# satshakit-mega.net
KiCad netlist of a schematic drawn in EAGLE
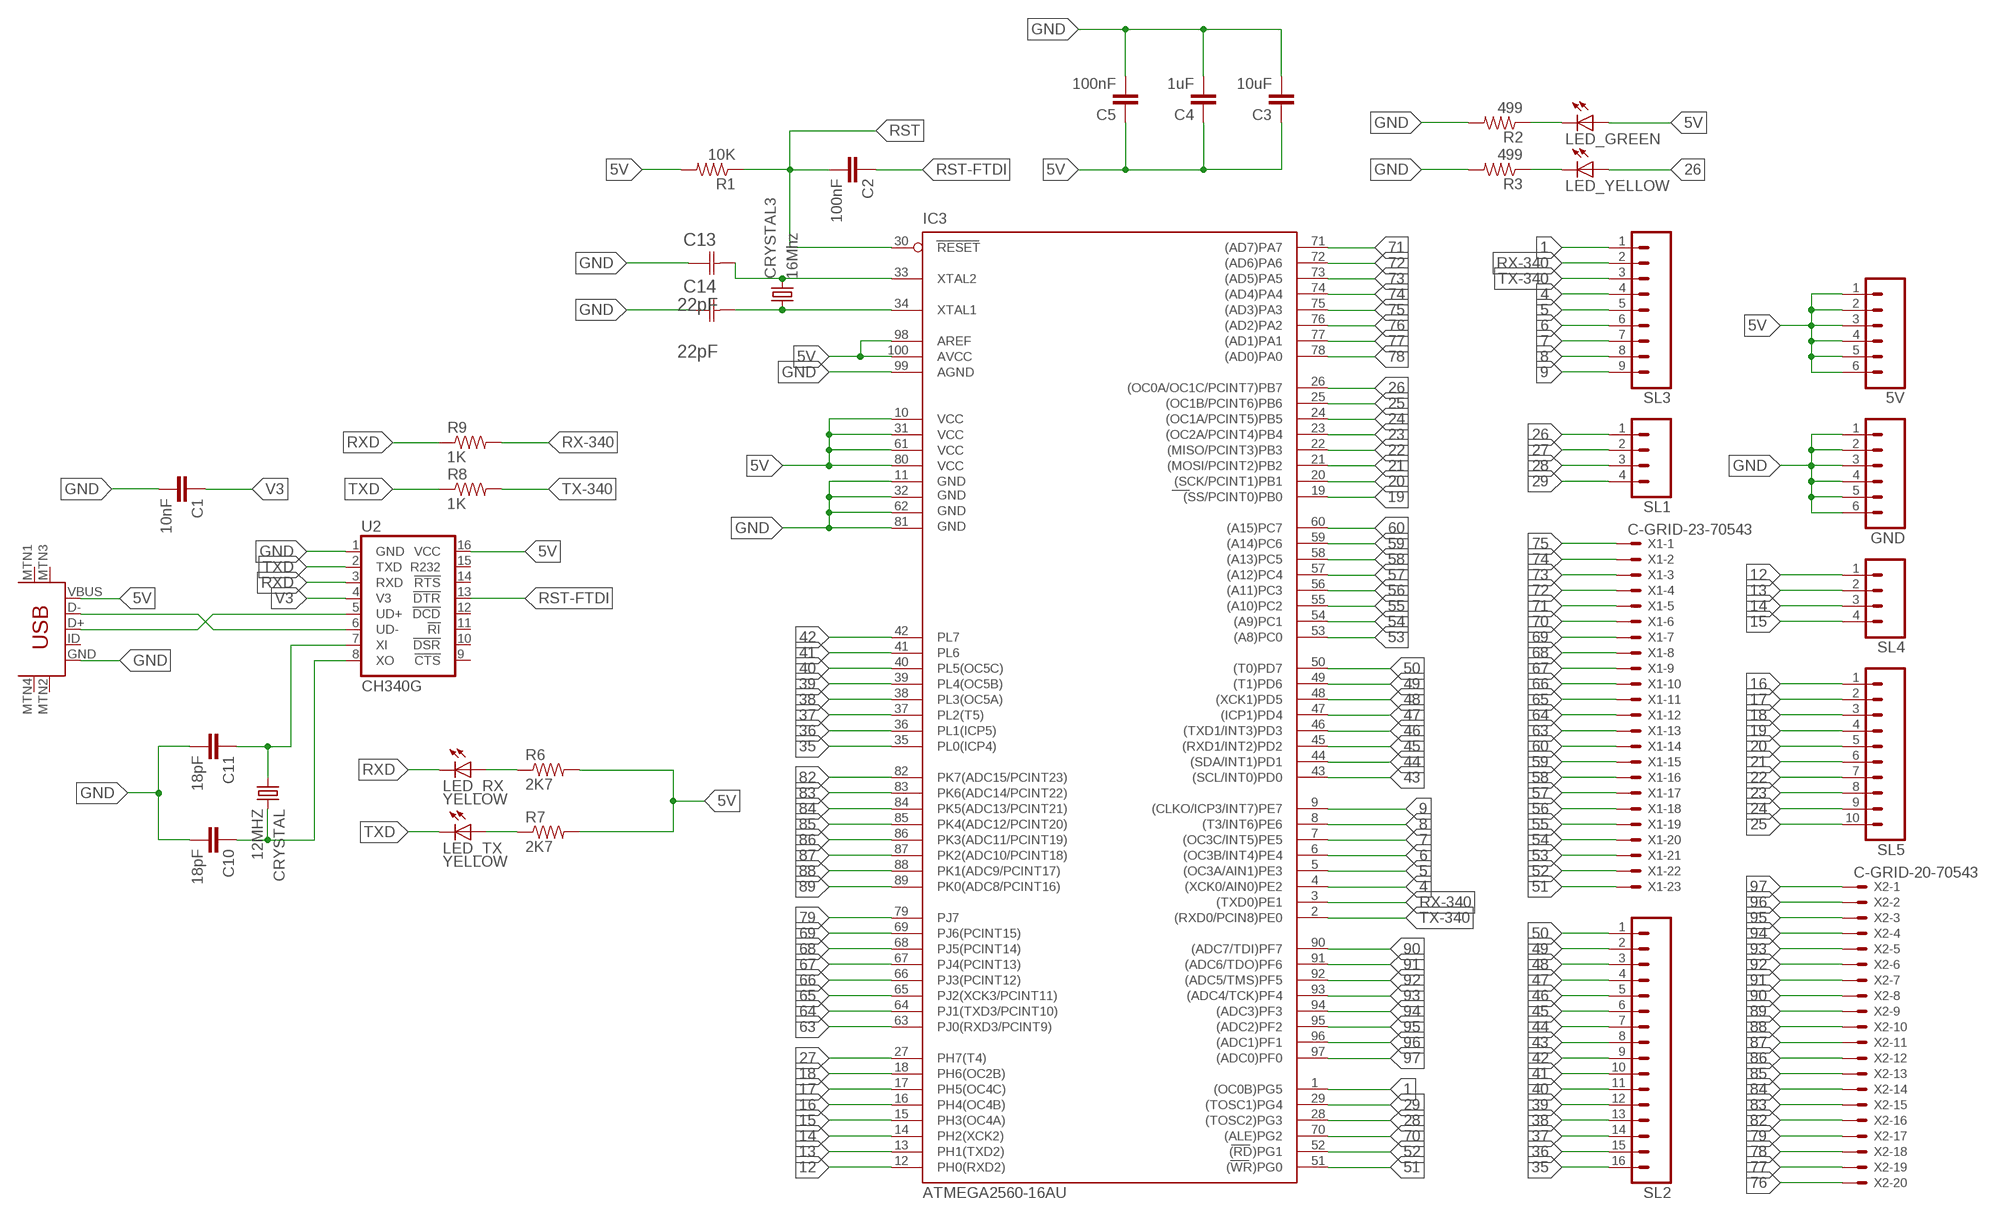
[diagram p0: schematic, sheet 1]

(export (version "E")
  (design (tool "Eeschema 10.0.6"))
  (components
    (comp (ref "5V")
      (value "M06")
      (footprint "eagle-import:06P")
      (libsource (lib "eagle-import") (part "M06"))
    )
    (comp (ref "C1")
      (value "10nF")
      (footprint "eagle-import:1206")
      (libsource (lib "eagle-import") (part "CAP1206"))
    )
    (comp (ref "C2")
      (value "100nF")
      (footprint "eagle-import:1206")
      (libsource (lib "eagle-import") (part "CAP1206"))
    )
    (comp (ref "C3")
      (value "10uF")
      (footprint "eagle-import:1206")
      (libsource (lib "eagle-import") (part "CAP1206"))
    )
    (comp (ref "C4")
      (value "1uF")
      (footprint "eagle-import:1206")
      (libsource (lib "eagle-import") (part "CAP1206"))
    )
    (comp (ref "C5")
      (value "100nF")
      (footprint "eagle-import:1206")
      (libsource (lib "eagle-import") (part "CAP1206"))
    )
    (comp (ref "C10")
      (value "18pF")
      (footprint "eagle-import:1206")
      (libsource (lib "eagle-import") (part "CAP1206"))
    )
    (comp (ref "C11")
      (value "18pF")
      (footprint "eagle-import:1206")
      (libsource (lib "eagle-import") (part "CAP1206"))
    )
    (comp (ref "C13")
      (value "22pF")
      (footprint "eagle-import:CAPC3216X178N")
      (fields (field (name "MPN") "0612ZC225MAT2A") (field (name "TOLERANCE") "±20%"))
      (libsource (lib "eagle-import") (part "0612ZC225MAT2A"))
    )
    (comp (ref "C14")
      (value "22pF")
      (footprint "eagle-import:CAPC3216X178N")
      (fields (field (name "MPN") "0612ZC225MAT2A") (field (name "TOLERANCE") "±20%"))
      (libsource (lib "eagle-import") (part "0612ZC225MAT2A"))
    )
    (comp (ref "CRYSTAL")
      (value "12MHZ")
      (footprint "eagle-import:CSM-7X-DU")
      (libsource (lib "eagle-import") (part "flight_controller.lbr01_FAB_Hello_CSM-7X-DU"))
    )
    (comp (ref "CRYSTAL3")
      (value "16Mhz")
      (footprint "eagle-import:CSM-7X-DU")
      (libsource (lib "eagle-import") (part "CSM-7X-DU"))
    )
    (comp (ref "GND")
      (value "M06")
      (footprint "eagle-import:06P")
      (libsource (lib "eagle-import") (part "M06"))
    )
    (comp (ref "IC3")
      (value "ATMEGA2560-16AU")
      (footprint "eagle-import:TQFP100")
      (libsource (lib "eagle-import") (part "ATMEGAAU1280-16"))
    )
    (comp (ref "LED_GREEN")
      (value "LED1206")
      (footprint "eagle-import:1206")
      (libsource (lib "eagle-import") (part "LED1206"))
    )
    (comp (ref "LED_RX")
      (value "YELLOW")
      (footprint "eagle-import:LED1206")
      (libsource (lib "eagle-import") (part "LED"))
    )
    (comp (ref "LED_TX")
      (value "YELLOW")
      (footprint "eagle-import:LED1206")
      (libsource (lib "eagle-import") (part "LED"))
    )
    (comp (ref "LED_YELLOW")
      (value "LED1206")
      (footprint "eagle-import:1206")
      (libsource (lib "eagle-import") (part "LED1206"))
    )
    (comp (ref "R1")
      (value "10K")
      (footprint "eagle-import:R1206")
      (libsource (lib "eagle-import") (part "RES-US1206"))
    )
    (comp (ref "R2")
      (value "499")
      (footprint "eagle-import:1206")
      (libsource (lib "eagle-import") (part "RESISTOR1206"))
    )
    (comp (ref "R3")
      (value "499")
      (footprint "eagle-import:1206")
      (libsource (lib "eagle-import") (part "RESISTOR1206"))
    )
    (comp (ref "R6")
      (value "2K7")
      (footprint "eagle-import:R1206")
      (libsource (lib "eagle-import") (part "RES-US1206"))
    )
    (comp (ref "R7")
      (value "2K7")
      (footprint "eagle-import:R1206")
      (libsource (lib "eagle-import") (part "RES-US1206"))
    )
    (comp (ref "R8")
      (value "1K")
      (footprint "eagle-import:R1206")
      (libsource (lib "eagle-import") (part "RES-US1206"))
    )
    (comp (ref "R9")
      (value "1K")
      (footprint "eagle-import:R1206")
      (libsource (lib "eagle-import") (part "RES-US1206"))
    )
    (comp (ref "SL1")
      (value "M04")
      (footprint "eagle-import:04P")
      (libsource (lib "eagle-import") (part "M04"))
    )
    (comp (ref "SL2")
      (value "M16")
      (footprint "eagle-import:16P")
      (libsource (lib "eagle-import") (part "M16"))
    )
    (comp (ref "SL3")
      (value "M09")
      (footprint "eagle-import:09P")
      (libsource (lib "eagle-import") (part "M09"))
    )
    (comp (ref "SL4")
      (value "M04")
      (footprint "eagle-import:04P")
      (libsource (lib "eagle-import") (part "M04"))
    )
    (comp (ref "SL5")
      (value "M10")
      (footprint "eagle-import:10P")
      (libsource (lib "eagle-import") (part "M10"))
    )
    (comp (ref "U$7")
      (value "USB-MINIB-5PIN")
      (footprint "eagle-import:USB-MINIB")
      (libsource (lib "eagle-import") (part "USB-MINIB-5PIN"))
    )
    (comp (ref "U2")
      (value "CH340G")
      (footprint "eagle-import:SO016")
      (libsource (lib "eagle-import") (part "CH340GSMD"))
    )
    (comp (ref "X1")
      (value "C-GRID-23-70543")
      (footprint "eagle-import:70543-23")
      (libsource (lib "eagle-import") (part "C-GRID-23-70543"))
    )
    (comp (ref "X2")
      (value "C-GRID-20-70543")
      (footprint "eagle-import:70543-20")
      (libsource (lib "eagle-import") (part "C-GRID-20-70543"))
    )
  )
  (nets
    (net (code "1") (name "1") (class "Default")
      (node (ref "IC3") (pin "1") (pinfunction "(OC0B)PG5_1") (pintype "bidirectional"))
      (node (ref "SL3") (pin "1") (pinfunction "1_1") (pintype "passive"))
    )
    (net (code "2") (name "4") (class "Default")
      (node (ref "IC3") (pin "4") (pinfunction "(XCK0/AIN0)PE2_4") (pintype "bidirectional"))
      (node (ref "SL3") (pin "4") (pinfunction "4_4") (pintype "passive"))
    )
    (net (code "3") (name "5") (class "Default")
      (node (ref "IC3") (pin "5") (pinfunction "(OC3A/AIN1)PE3_5") (pintype "bidirectional"))
      (node (ref "SL3") (pin "5") (pinfunction "5_5") (pintype "passive"))
    )
    (net (code "4") (name "5V") (class "Default")
      (node (ref "5V") (pin "1") (pinfunction "1_1") (pintype "passive"))
      (node (ref "5V") (pin "2") (pinfunction "2_2") (pintype "passive"))
      (node (ref "5V") (pin "3") (pinfunction "3_3") (pintype "passive"))
      (node (ref "5V") (pin "4") (pinfunction "4_4") (pintype "passive"))
      (node (ref "5V") (pin "5") (pinfunction "5_5") (pintype "passive"))
      (node (ref "5V") (pin "6") (pinfunction "6_6") (pintype "passive"))
      (node (ref "C3") (pin "1") (pinfunction "1_1") (pintype "passive"))
      (node (ref "C4") (pin "1") (pinfunction "1_1") (pintype "passive"))
      (node (ref "C5") (pin "1") (pinfunction "1_1") (pintype "passive"))
      (node (ref "IC3") (pin "10") (pinfunction "VCC_10") (pintype "power_in"))
      (node (ref "IC3") (pin "100") (pinfunction "AVCC_100") (pintype "power_in"))
      (node (ref "IC3") (pin "31") (pinfunction "VCC1_31") (pintype "power_in"))
      (node (ref "IC3") (pin "61") (pinfunction "VCC2_61") (pintype "power_in"))
      (node (ref "IC3") (pin "80") (pinfunction "VCC3_80") (pintype "power_in"))
      (node (ref "IC3") (pin "98") (pinfunction "AREF_98") (pintype "bidirectional"))
      (node (ref "LED_GREEN") (pin "1") (pinfunction "A_1") (pintype "passive"))
      (node (ref "R1") (pin "2") (pinfunction "2_2") (pintype "passive"))
      (node (ref "R6") (pin "2") (pinfunction "2_2") (pintype "passive"))
      (node (ref "R7") (pin "2") (pinfunction "2_2") (pintype "passive"))
      (node (ref "U$7") (pin "VBUS") (pinfunction "VBUS_VBUS") (pintype "bidirectional"))
      (node (ref "U2") (pin "16") (pinfunction "VCC_16") (pintype "bidirectional"))
    )
    (net (code "5") (name "6") (class "Default")
      (node (ref "IC3") (pin "6") (pinfunction "(OC3B/INT4)PE4_6") (pintype "bidirectional"))
      (node (ref "SL3") (pin "6") (pinfunction "6_6") (pintype "passive"))
    )
    (net (code "6") (name "7") (class "Default")
      (node (ref "IC3") (pin "7") (pinfunction "(OC3C/INT5)PE5_7") (pintype "bidirectional"))
      (node (ref "SL3") (pin "7") (pinfunction "7_7") (pintype "passive"))
    )
    (net (code "7") (name "8") (class "Default")
      (node (ref "IC3") (pin "8") (pinfunction "(T3/INT6)PE6_8") (pintype "bidirectional"))
      (node (ref "SL3") (pin "8") (pinfunction "8_8") (pintype "passive"))
    )
    (net (code "8") (name "9") (class "Default")
      (node (ref "IC3") (pin "9") (pinfunction "(CLKO/ICP3/INT7)PE7_9") (pintype "bidirectional"))
      (node (ref "SL3") (pin "9") (pinfunction "9_9") (pintype "passive"))
    )
    (net (code "9") (name "12") (class "Default")
      (node (ref "IC3") (pin "12") (pinfunction "PH0(RXD2)_12") (pintype "bidirectional"))
      (node (ref "SL4") (pin "1") (pinfunction "1_1") (pintype "passive"))
    )
    (net (code "10") (name "13") (class "Default")
      (node (ref "IC3") (pin "13") (pinfunction "PH1(TXD2)_13") (pintype "bidirectional"))
      (node (ref "SL4") (pin "2") (pinfunction "2_2") (pintype "passive"))
    )
    (net (code "11") (name "14") (class "Default")
      (node (ref "IC3") (pin "14") (pinfunction "PH2(XCK2)_14") (pintype "bidirectional"))
      (node (ref "SL4") (pin "3") (pinfunction "3_3") (pintype "passive"))
    )
    (net (code "12") (name "15") (class "Default")
      (node (ref "IC3") (pin "15") (pinfunction "PH3(OC4A)_15") (pintype "bidirectional"))
      (node (ref "SL4") (pin "4") (pinfunction "4_4") (pintype "passive"))
    )
    (net (code "13") (name "16") (class "Default")
      (node (ref "IC3") (pin "16") (pinfunction "PH4(OC4B)_16") (pintype "bidirectional"))
      (node (ref "SL5") (pin "1") (pinfunction "1_1") (pintype "passive"))
    )
    (net (code "14") (name "17") (class "Default")
      (node (ref "IC3") (pin "17") (pinfunction "PH5(OC4C)_17") (pintype "bidirectional"))
      (node (ref "SL5") (pin "2") (pinfunction "2_2") (pintype "passive"))
    )
    (net (code "15") (name "18") (class "Default")
      (node (ref "IC3") (pin "18") (pinfunction "PH6(OC2B)_18") (pintype "bidirectional"))
      (node (ref "SL5") (pin "3") (pinfunction "3_3") (pintype "passive"))
    )
    (net (code "16") (name "19") (class "Default")
      (node (ref "IC3") (pin "19") (pinfunction "(SS/PCINT0)PB0_19") (pintype "bidirectional"))
      (node (ref "SL5") (pin "4") (pinfunction "4_4") (pintype "passive"))
    )
    (net (code "17") (name "20") (class "Default")
      (node (ref "IC3") (pin "20") (pinfunction "(SCK/PCINT1)PB1_20") (pintype "bidirectional"))
      (node (ref "SL5") (pin "5") (pinfunction "5_5") (pintype "passive"))
    )
    (net (code "18") (name "21") (class "Default")
      (node (ref "IC3") (pin "21") (pinfunction "(MOSI/PCINT2)PB2_21") (pintype "bidirectional"))
      (node (ref "SL5") (pin "6") (pinfunction "6_6") (pintype "passive"))
    )
    (net (code "19") (name "22") (class "Default")
      (node (ref "IC3") (pin "22") (pinfunction "(MISO/PCINT3)PB3_22") (pintype "bidirectional"))
      (node (ref "SL5") (pin "7") (pinfunction "7_7") (pintype "passive"))
    )
    (net (code "20") (name "23") (class "Default")
      (node (ref "IC3") (pin "23") (pinfunction "(OC2A/PCINT4)PB4_23") (pintype "bidirectional"))
      (node (ref "SL5") (pin "8") (pinfunction "8_8") (pintype "passive"))
    )
    (net (code "21") (name "24") (class "Default")
      (node (ref "IC3") (pin "24") (pinfunction "(OC1A/PCINT5)PB5_24") (pintype "bidirectional"))
      (node (ref "SL5") (pin "9") (pinfunction "9_9") (pintype "passive"))
    )
    (net (code "22") (name "25") (class "Default")
      (node (ref "IC3") (pin "25") (pinfunction "(OC1B/PCINT6)PB6_25") (pintype "bidirectional"))
      (node (ref "SL5") (pin "10") (pinfunction "10_10") (pintype "passive"))
    )
    (net (code "23") (name "26") (class "Default")
      (node (ref "IC3") (pin "26") (pinfunction "(OC0A/OC1C/PCINT7)PB7_26") (pintype "bidirectional"))
      (node (ref "LED_YELLOW") (pin "1") (pinfunction "A_1") (pintype "passive"))
      (node (ref "SL1") (pin "1") (pinfunction "1_1") (pintype "passive"))
    )
    (net (code "24") (name "27") (class "Default")
      (node (ref "IC3") (pin "27") (pinfunction "PH7(T4)_27") (pintype "bidirectional"))
      (node (ref "SL1") (pin "2") (pinfunction "2_2") (pintype "passive"))
    )
    (net (code "25") (name "28") (class "Default")
      (node (ref "IC3") (pin "28") (pinfunction "(TOSC2)PG3_28") (pintype "bidirectional"))
      (node (ref "SL1") (pin "3") (pinfunction "3_3") (pintype "passive"))
    )
    (net (code "26") (name "29") (class "Default")
      (node (ref "IC3") (pin "29") (pinfunction "(TOSC1)PG4_29") (pintype "bidirectional"))
      (node (ref "SL1") (pin "4") (pinfunction "4_4") (pintype "passive"))
    )
    (net (code "27") (name "35") (class "Default")
      (node (ref "IC3") (pin "35") (pinfunction "PL0(ICP4)_35") (pintype "bidirectional"))
      (node (ref "SL2") (pin "16") (pinfunction "16_16") (pintype "passive"))
    )
    (net (code "28") (name "36") (class "Default")
      (node (ref "IC3") (pin "36") (pinfunction "PL1(ICP5)_36") (pintype "bidirectional"))
      (node (ref "SL2") (pin "15") (pinfunction "15_15") (pintype "passive"))
    )
    (net (code "29") (name "37") (class "Default")
      (node (ref "IC3") (pin "37") (pinfunction "PL2(T5)_37") (pintype "bidirectional"))
      (node (ref "SL2") (pin "14") (pinfunction "14_14") (pintype "passive"))
    )
    (net (code "30") (name "38") (class "Default")
      (node (ref "IC3") (pin "38") (pinfunction "PL3(OC5A)_38") (pintype "bidirectional"))
      (node (ref "SL2") (pin "13") (pinfunction "13_13") (pintype "passive"))
    )
    (net (code "31") (name "39") (class "Default")
      (node (ref "IC3") (pin "39") (pinfunction "PL4(OC5B)_39") (pintype "bidirectional"))
      (node (ref "SL2") (pin "12") (pinfunction "12_12") (pintype "passive"))
    )
    (net (code "32") (name "40") (class "Default")
      (node (ref "IC3") (pin "40") (pinfunction "PL5(OC5C)_40") (pintype "bidirectional"))
      (node (ref "SL2") (pin "11") (pinfunction "11_11") (pintype "passive"))
    )
    (net (code "33") (name "41") (class "Default")
      (node (ref "IC3") (pin "41") (pinfunction "PL6_41") (pintype "bidirectional"))
      (node (ref "SL2") (pin "10") (pinfunction "10_10") (pintype "passive"))
    )
    (net (code "34") (name "42") (class "Default")
      (node (ref "IC3") (pin "42") (pinfunction "PL7_42") (pintype "bidirectional"))
      (node (ref "SL2") (pin "9") (pinfunction "9_9") (pintype "passive"))
    )
    (net (code "35") (name "43") (class "Default")
      (node (ref "IC3") (pin "43") (pinfunction "(SCL/INT0)PD0_43") (pintype "bidirectional"))
      (node (ref "SL2") (pin "8") (pinfunction "8_8") (pintype "passive"))
    )
    (net (code "36") (name "44") (class "Default")
      (node (ref "IC3") (pin "44") (pinfunction "(SDA/INT1)PD1_44") (pintype "bidirectional"))
      (node (ref "SL2") (pin "7") (pinfunction "7_7") (pintype "passive"))
    )
    (net (code "37") (name "45") (class "Default")
      (node (ref "IC3") (pin "45") (pinfunction "(RXD1/INT2)PD2_45") (pintype "bidirectional"))
      (node (ref "SL2") (pin "6") (pinfunction "6_6") (pintype "passive"))
    )
    (net (code "38") (name "46") (class "Default")
      (node (ref "IC3") (pin "46") (pinfunction "(TXD1/INT3)PD3_46") (pintype "bidirectional"))
      (node (ref "SL2") (pin "5") (pinfunction "5_5") (pintype "passive"))
    )
    (net (code "39") (name "47") (class "Default")
      (node (ref "IC3") (pin "47") (pinfunction "(ICP1)PD4_47") (pintype "bidirectional"))
      (node (ref "SL2") (pin "4") (pinfunction "4_4") (pintype "passive"))
    )
    (net (code "40") (name "48") (class "Default")
      (node (ref "IC3") (pin "48") (pinfunction "(XCK1)PD5_48") (pintype "bidirectional"))
      (node (ref "SL2") (pin "3") (pinfunction "3_3") (pintype "passive"))
    )
    (net (code "41") (name "49") (class "Default")
      (node (ref "IC3") (pin "49") (pinfunction "(T1)PD6_49") (pintype "bidirectional"))
      (node (ref "SL2") (pin "2") (pinfunction "2_2") (pintype "passive"))
    )
    (net (code "42") (name "50") (class "Default")
      (node (ref "IC3") (pin "50") (pinfunction "(T0)PD7_50") (pintype "bidirectional"))
      (node (ref "SL2") (pin "1") (pinfunction "1_1") (pintype "passive"))
    )
    (net (code "43") (name "51") (class "Default")
      (node (ref "IC3") (pin "51") (pinfunction "(WR)PG0_51") (pintype "bidirectional"))
      (node (ref "X1") (pin "23") (pinfunction "S_23") (pintype "passive"))
    )
    (net (code "44") (name "52") (class "Default")
      (node (ref "IC3") (pin "52") (pinfunction "(RD)PG1_52") (pintype "bidirectional"))
      (node (ref "X1") (pin "22") (pinfunction "S_22") (pintype "passive"))
    )
    (net (code "45") (name "53") (class "Default")
      (node (ref "IC3") (pin "53") (pinfunction "(A8)PC0_53") (pintype "bidirectional"))
      (node (ref "X1") (pin "21") (pinfunction "S_21") (pintype "passive"))
    )
    (net (code "46") (name "54") (class "Default")
      (node (ref "IC3") (pin "54") (pinfunction "(A9)PC1_54") (pintype "bidirectional"))
      (node (ref "X1") (pin "20") (pinfunction "S_20") (pintype "passive"))
    )
    (net (code "47") (name "55") (class "Default")
      (node (ref "IC3") (pin "55") (pinfunction "(A10)PC2_55") (pintype "bidirectional"))
      (node (ref "X1") (pin "19") (pinfunction "S_19") (pintype "passive"))
    )
    (net (code "48") (name "56") (class "Default")
      (node (ref "IC3") (pin "56") (pinfunction "(A11)PC3_56") (pintype "bidirectional"))
      (node (ref "X1") (pin "18") (pinfunction "S_18") (pintype "passive"))
    )
    (net (code "49") (name "57") (class "Default")
      (node (ref "IC3") (pin "57") (pinfunction "(A12)PC4_57") (pintype "bidirectional"))
      (node (ref "X1") (pin "17") (pinfunction "S_17") (pintype "passive"))
    )
    (net (code "50") (name "58") (class "Default")
      (node (ref "IC3") (pin "58") (pinfunction "(A13)PC5_58") (pintype "bidirectional"))
      (node (ref "X1") (pin "16") (pinfunction "S_16") (pintype "passive"))
    )
    (net (code "51") (name "59") (class "Default")
      (node (ref "IC3") (pin "59") (pinfunction "(A14)PC6_59") (pintype "bidirectional"))
      (node (ref "X1") (pin "15") (pinfunction "S_15") (pintype "passive"))
    )
    (net (code "52") (name "60") (class "Default")
      (node (ref "IC3") (pin "60") (pinfunction "(A15)PC7_60") (pintype "bidirectional"))
      (node (ref "X1") (pin "14") (pinfunction "S_14") (pintype "passive"))
    )
    (net (code "53") (name "63") (class "Default")
      (node (ref "IC3") (pin "63") (pinfunction "PJ0(RXD3/PCINT9)_63") (pintype "bidirectional"))
      (node (ref "X1") (pin "13") (pinfunction "S_13") (pintype "passive"))
    )
    (net (code "54") (name "64") (class "Default")
      (node (ref "IC3") (pin "64") (pinfunction "PJ1(TXD3/PCINT10)_64") (pintype "bidirectional"))
      (node (ref "X1") (pin "12") (pinfunction "S_12") (pintype "passive"))
    )
    (net (code "55") (name "65") (class "Default")
      (node (ref "IC3") (pin "65") (pinfunction "PJ2(XCK3/PCINT11)_65") (pintype "bidirectional"))
      (node (ref "X1") (pin "11") (pinfunction "S_11") (pintype "passive"))
    )
    (net (code "56") (name "66") (class "Default")
      (node (ref "IC3") (pin "66") (pinfunction "PJ3(PCINT12)_66") (pintype "bidirectional"))
      (node (ref "X1") (pin "10") (pinfunction "S_10") (pintype "passive"))
    )
    (net (code "57") (name "67") (class "Default")
      (node (ref "IC3") (pin "67") (pinfunction "PJ4(PCINT13)_67") (pintype "bidirectional"))
      (node (ref "X1") (pin "9") (pinfunction "S_9") (pintype "passive"))
    )
    (net (code "58") (name "68") (class "Default")
      (node (ref "IC3") (pin "68") (pinfunction "PJ5(PCINT14)_68") (pintype "bidirectional"))
      (node (ref "X1") (pin "8") (pinfunction "S_8") (pintype "passive"))
    )
    (net (code "59") (name "69") (class "Default")
      (node (ref "IC3") (pin "69") (pinfunction "PJ6(PCINT15)_69") (pintype "bidirectional"))
      (node (ref "X1") (pin "7") (pinfunction "S_7") (pintype "passive"))
    )
    (net (code "60") (name "70") (class "Default")
      (node (ref "IC3") (pin "70") (pinfunction "(ALE)PG2_70") (pintype "bidirectional"))
      (node (ref "X1") (pin "6") (pinfunction "S_6") (pintype "passive"))
    )
    (net (code "61") (name "71") (class "Default")
      (node (ref "IC3") (pin "71") (pinfunction "(AD7)PA7_71") (pintype "bidirectional"))
      (node (ref "X1") (pin "5") (pinfunction "S_5") (pintype "passive"))
    )
    (net (code "62") (name "72") (class "Default")
      (node (ref "IC3") (pin "72") (pinfunction "(AD6)PA6_72") (pintype "bidirectional"))
      (node (ref "X1") (pin "4") (pinfunction "S_4") (pintype "passive"))
    )
    (net (code "63") (name "73") (class "Default")
      (node (ref "IC3") (pin "73") (pinfunction "(AD5)PA5_73") (pintype "bidirectional"))
      (node (ref "X1") (pin "3") (pinfunction "S_3") (pintype "passive"))
    )
    (net (code "64") (name "74") (class "Default")
      (node (ref "IC3") (pin "74") (pinfunction "(AD4)PA4_74") (pintype "bidirectional"))
      (node (ref "X1") (pin "2") (pinfunction "S_2") (pintype "passive"))
    )
    (net (code "65") (name "75") (class "Default")
      (node (ref "IC3") (pin "75") (pinfunction "(AD3)PA3_75") (pintype "bidirectional"))
      (node (ref "X1") (pin "1") (pinfunction "S_1") (pintype "passive"))
    )
    (net (code "66") (name "76") (class "Default")
      (node (ref "IC3") (pin "76") (pinfunction "(AD2)PA2_76") (pintype "bidirectional"))
      (node (ref "X2") (pin "20") (pinfunction "S_20") (pintype "passive"))
    )
    (net (code "67") (name "77") (class "Default")
      (node (ref "IC3") (pin "77") (pinfunction "(AD1)PA1_77") (pintype "bidirectional"))
      (node (ref "X2") (pin "19") (pinfunction "S_19") (pintype "passive"))
    )
    (net (code "68") (name "78") (class "Default")
      (node (ref "IC3") (pin "78") (pinfunction "(AD0)PA0_78") (pintype "bidirectional"))
      (node (ref "X2") (pin "18") (pinfunction "S_18") (pintype "passive"))
    )
    (net (code "69") (name "79") (class "Default")
      (node (ref "IC3") (pin "79") (pinfunction "PJ7_79") (pintype "bidirectional"))
      (node (ref "X2") (pin "17") (pinfunction "S_17") (pintype "passive"))
    )
    (net (code "70") (name "82") (class "Default")
      (node (ref "IC3") (pin "82") (pinfunction "PK7(ADC15/PCINT23)_82") (pintype "bidirectional"))
      (node (ref "X2") (pin "16") (pinfunction "S_16") (pintype "passive"))
    )
    (net (code "71") (name "83") (class "Default")
      (node (ref "IC3") (pin "83") (pinfunction "PK6(ADC14/PCINT22)_83") (pintype "bidirectional"))
      (node (ref "X2") (pin "15") (pinfunction "S_15") (pintype "passive"))
    )
    (net (code "72") (name "84") (class "Default")
      (node (ref "IC3") (pin "84") (pinfunction "PK5(ADC13/PCINT21)_84") (pintype "bidirectional"))
      (node (ref "X2") (pin "14") (pinfunction "S_14") (pintype "passive"))
    )
    (net (code "73") (name "85") (class "Default")
      (node (ref "IC3") (pin "85") (pinfunction "PK4(ADC12/PCINT20)_85") (pintype "bidirectional"))
      (node (ref "X2") (pin "13") (pinfunction "S_13") (pintype "passive"))
    )
    (net (code "74") (name "86") (class "Default")
      (node (ref "IC3") (pin "86") (pinfunction "PK3(ADC11/PCINT19)_86") (pintype "bidirectional"))
      (node (ref "X2") (pin "12") (pinfunction "S_12") (pintype "passive"))
    )
    (net (code "75") (name "87") (class "Default")
      (node (ref "IC3") (pin "87") (pinfunction "PK2(ADC10/PCINT18)_87") (pintype "bidirectional"))
      (node (ref "X2") (pin "11") (pinfunction "S_11") (pintype "passive"))
    )
    (net (code "76") (name "88") (class "Default")
      (node (ref "IC3") (pin "88") (pinfunction "PK1(ADC9/PCINT17)_88") (pintype "bidirectional"))
      (node (ref "X2") (pin "10") (pinfunction "S_10") (pintype "passive"))
    )
    (net (code "77") (name "89") (class "Default")
      (node (ref "IC3") (pin "89") (pinfunction "PK0(ADC8/PCINT16)_89") (pintype "bidirectional"))
      (node (ref "X2") (pin "9") (pinfunction "S_9") (pintype "passive"))
    )
    (net (code "78") (name "90") (class "Default")
      (node (ref "IC3") (pin "90") (pinfunction "(ADC7/TDI)PF7_90") (pintype "bidirectional"))
      (node (ref "X2") (pin "8") (pinfunction "S_8") (pintype "passive"))
    )
    (net (code "79") (name "91") (class "Default")
      (node (ref "IC3") (pin "91") (pinfunction "(ADC6/TDO)PF6_91") (pintype "bidirectional"))
      (node (ref "X2") (pin "7") (pinfunction "S_7") (pintype "passive"))
    )
    (net (code "80") (name "92") (class "Default")
      (node (ref "IC3") (pin "92") (pinfunction "(ADC5/TMS)PF5_92") (pintype "bidirectional"))
      (node (ref "X2") (pin "6") (pinfunction "S_6") (pintype "passive"))
    )
    (net (code "81") (name "93") (class "Default")
      (node (ref "IC3") (pin "93") (pinfunction "(ADC4/TCK)PF4_93") (pintype "bidirectional"))
      (node (ref "X2") (pin "5") (pinfunction "S_5") (pintype "passive"))
    )
    (net (code "82") (name "94") (class "Default")
      (node (ref "IC3") (pin "94") (pinfunction "(ADC3)PF3_94") (pintype "bidirectional"))
      (node (ref "X2") (pin "4") (pinfunction "S_4") (pintype "passive"))
    )
    (net (code "83") (name "95") (class "Default")
      (node (ref "IC3") (pin "95") (pinfunction "(ADC2)PF2_95") (pintype "bidirectional"))
      (node (ref "X2") (pin "3") (pinfunction "S_3") (pintype "passive"))
    )
    (net (code "84") (name "96") (class "Default")
      (node (ref "IC3") (pin "96") (pinfunction "(ADC1)PF1_96") (pintype "bidirectional"))
      (node (ref "X2") (pin "2") (pinfunction "S_2") (pintype "passive"))
    )
    (net (code "85") (name "97") (class "Default")
      (node (ref "IC3") (pin "97") (pinfunction "(ADC0)PF0_97") (pintype "bidirectional"))
      (node (ref "X2") (pin "1") (pinfunction "S_1") (pintype "passive"))
    )
    (net (code "86") (name "GND") (class "Default")
      (node (ref "C1") (pin "2") (pinfunction "2_2") (pintype "passive"))
      (node (ref "C10") (pin "2") (pinfunction "2_2") (pintype "passive"))
      (node (ref "C11") (pin "2") (pinfunction "2_2") (pintype "passive"))
      (node (ref "C13") (pin "1") (pinfunction "C1_1") (pintype "passive"))
      (node (ref "C14") (pin "1") (pinfunction "C1_1") (pintype "passive"))
      (node (ref "C3") (pin "2") (pinfunction "2_2") (pintype "passive"))
      (node (ref "C4") (pin "2") (pinfunction "2_2") (pintype "passive"))
      (node (ref "C5") (pin "2") (pinfunction "2_2") (pintype "passive"))
      (node (ref "GND") (pin "1") (pinfunction "1_1") (pintype "passive"))
      (node (ref "GND") (pin "2") (pinfunction "2_2") (pintype "passive"))
      (node (ref "GND") (pin "3") (pinfunction "3_3") (pintype "passive"))
      (node (ref "GND") (pin "4") (pinfunction "4_4") (pintype "passive"))
      (node (ref "GND") (pin "5") (pinfunction "5_5") (pintype "passive"))
      (node (ref "GND") (pin "6") (pinfunction "6_6") (pintype "passive"))
      (node (ref "IC3") (pin "11") (pinfunction "GND_11") (pintype "power_in"))
      (node (ref "IC3") (pin "32") (pinfunction "GND1_32") (pintype "power_in"))
      (node (ref "IC3") (pin "62") (pinfunction "GND2_62") (pintype "power_in"))
      (node (ref "IC3") (pin "81") (pinfunction "GND3_81") (pintype "power_in"))
      (node (ref "IC3") (pin "99") (pinfunction "AGND_99") (pintype "power_in"))
      (node (ref "R2") (pin "2") (pinfunction "2_2") (pintype "passive"))
      (node (ref "R3") (pin "2") (pinfunction "2_2") (pintype "passive"))
      (node (ref "U$7") (pin "GND") (pinfunction "GND_GND") (pintype "bidirectional"))
      (node (ref "U2") (pin "1") (pinfunction "GND_1") (pintype "bidirectional"))
    )
    (net (code "87") (name "Net-(C13-C2)") (class "Default")
      (node (ref "C13") (pin "2") (pinfunction "C2_2") (pintype "passive"))
      (node (ref "CRYSTAL3") (pin "2") (pinfunction "2_2") (pintype "passive"))
      (node (ref "IC3") (pin "33") (pinfunction "XTAL2_33") (pintype "output"))
    )
    (net (code "88") (name "Net-(C14-C2)") (class "Default")
      (node (ref "C14") (pin "2") (pinfunction "C2_2") (pintype "passive"))
      (node (ref "CRYSTAL3") (pin "1") (pinfunction "1_1") (pintype "passive"))
      (node (ref "IC3") (pin "34") (pinfunction "XTAL1_34") (pintype "input"))
    )
    (net (code "89") (name "Net-(LED_GREEN-C)") (class "Default")
      (node (ref "LED_GREEN") (pin "2") (pinfunction "C_2") (pintype "passive"))
      (node (ref "R2") (pin "1") (pinfunction "1_1") (pintype "passive"))
    )
    (net (code "90") (name "Net-(LED_RX-A)") (class "Default")
      (node (ref "LED_RX") (pin "1") (pinfunction "A_1") (pintype "passive"))
      (node (ref "R6") (pin "1") (pinfunction "1_1") (pintype "passive"))
    )
    (net (code "91") (name "Net-(LED_TX-A)") (class "Default")
      (node (ref "LED_TX") (pin "1") (pinfunction "A_1") (pintype "passive"))
      (node (ref "R7") (pin "1") (pinfunction "1_1") (pintype "passive"))
    )
    (net (code "92") (name "Net-(LED_YELLOW-C)") (class "Default")
      (node (ref "LED_YELLOW") (pin "2") (pinfunction "C_2") (pintype "passive"))
      (node (ref "R3") (pin "1") (pinfunction "1_1") (pintype "passive"))
    )
    (net (code "93") (name "Net-(U2-UD+)") (class "Default")
      (node (ref "U$7") (pin "D+") (pinfunction "D+_D+") (pintype "bidirectional"))
      (node (ref "U2") (pin "5") (pinfunction "UD+_5") (pintype "bidirectional"))
    )
    (net (code "94") (name "Net-(U2-UD-)") (class "Default")
      (node (ref "U$7") (pin "D-") (pinfunction "D-_D-") (pintype "bidirectional"))
      (node (ref "U2") (pin "6") (pinfunction "UD-_6") (pintype "bidirectional"))
    )
    (net (code "95") (name "Net-(U2-XI)") (class "Default")
      (node (ref "C11") (pin "1") (pinfunction "1_1") (pintype "passive"))
      (node (ref "CRYSTAL") (pin "1") (pinfunction "1_1") (pintype "passive"))
      (node (ref "U2") (pin "7") (pinfunction "XI_7") (pintype "bidirectional"))
    )
    (net (code "96") (name "Net-(U2-XO)") (class "Default")
      (node (ref "C10") (pin "1") (pinfunction "1_1") (pintype "passive"))
      (node (ref "CRYSTAL") (pin "2") (pinfunction "2_2") (pintype "passive"))
      (node (ref "U2") (pin "8") (pinfunction "XO_8") (pintype "bidirectional"))
    )
    (net (code "97") (name "RST") (class "Default")
      (node (ref "C2") (pin "2") (pinfunction "2_2") (pintype "passive"))
      (node (ref "IC3") (pin "30") (pinfunction "RESET_30") (pintype "input"))
      (node (ref "R1") (pin "1") (pinfunction "1_1") (pintype "passive"))
    )
    (net (code "98") (name "RST-FTDI") (class "Default")
      (node (ref "C2") (pin "1") (pinfunction "1_1") (pintype "passive"))
      (node (ref "U2") (pin "13") (pinfunction "~{DTR}_13") (pintype "bidirectional"))
    )
    (net (code "99") (name "RX-340") (class "Default")
      (node (ref "IC3") (pin "3") (pinfunction "(TXD0)PE1_3") (pintype "bidirectional"))
      (node (ref "R9") (pin "2") (pinfunction "2_2") (pintype "passive"))
      (node (ref "SL3") (pin "2") (pinfunction "2_2") (pintype "passive"))
    )
    (net (code "100") (name "RXD") (class "Default")
      (node (ref "LED_RX") (pin "2") (pinfunction "C_2") (pintype "passive"))
      (node (ref "R9") (pin "1") (pinfunction "1_1") (pintype "passive"))
      (node (ref "U2") (pin "3") (pinfunction "RXD_3") (pintype "bidirectional"))
    )
    (net (code "101") (name "TX-340") (class "Default")
      (node (ref "IC3") (pin "2") (pinfunction "(RXD0/PCIN8)PE0_2") (pintype "bidirectional"))
      (node (ref "R8") (pin "2") (pinfunction "2_2") (pintype "passive"))
      (node (ref "SL3") (pin "3") (pinfunction "3_3") (pintype "passive"))
    )
    (net (code "102") (name "TXD") (class "Default")
      (node (ref "LED_TX") (pin "2") (pinfunction "C_2") (pintype "passive"))
      (node (ref "R8") (pin "1") (pinfunction "1_1") (pintype "passive"))
      (node (ref "U2") (pin "2") (pinfunction "TXD_2") (pintype "bidirectional"))
    )
    (net (code "103") (name "V3") (class "Default")
      (node (ref "C1") (pin "1") (pinfunction "1_1") (pintype "passive"))
      (node (ref "U2") (pin "4") (pinfunction "V3_4") (pintype "bidirectional"))
    )
    (net (code "104") (name "unconnected-(U$7-MTN1-PadMTN3)") (class "Default")
      (node (ref "U$7") (pin "MTN3") (pinfunction "MTN1_MTN3") (pintype "bidirectional"))
    )
    (net (code "105") (name "unconnected-(U$7-MTN2-PadMTN1)") (class "Default")
      (node (ref "U$7") (pin "MTN1") (pinfunction "MTN2_MTN1") (pintype "bidirectional"))
    )
    (net (code "106") (name "unconnected-(U$7-MTN3-PadMTN2)") (class "Default")
      (node (ref "U$7") (pin "MTN2") (pinfunction "MTN3_MTN2") (pintype "bidirectional"))
    )
    (net (code "107") (name "unconnected-(U$7-PadID)") (class "Default")
      (node (ref "U$7") (pin "ID") (pinfunction "ID_ID") (pintype "bidirectional"))
    )
    (net (code "108") (name "unconnected-(U$7-PadMTN4)") (class "Default")
      (node (ref "U$7") (pin "MTN4") (pinfunction "MTN4_MTN4") (pintype "bidirectional"))
    )
    (net (code "109") (name "unconnected-(U2-R232-Pad15)") (class "Default")
      (node (ref "U2") (pin "15") (pinfunction "R232_15") (pintype "bidirectional"))
    )
    (net (code "110") (name "unconnected-(U2-~{CTS}-Pad9)") (class "Default")
      (node (ref "U2") (pin "9") (pinfunction "~{CTS}_9") (pintype "bidirectional"))
    )
    (net (code "111") (name "unconnected-(U2-~{DCD}-Pad12)") (class "Default")
      (node (ref "U2") (pin "12") (pinfunction "~{DCD}_12") (pintype "bidirectional"))
    )
    (net (code "112") (name "unconnected-(U2-~{DSR}-Pad10)") (class "Default")
      (node (ref "U2") (pin "10") (pinfunction "~{DSR}_10") (pintype "bidirectional"))
    )
    (net (code "113") (name "unconnected-(U2-~{RI}-Pad11)") (class "Default")
      (node (ref "U2") (pin "11") (pinfunction "~{RI}_11") (pintype "bidirectional"))
    )
    (net (code "114") (name "unconnected-(U2-~{RTS}-Pad14)") (class "Default")
      (node (ref "U2") (pin "14") (pinfunction "~{RTS}_14") (pintype "bidirectional"))
    )
  )
)
